# Microcontroller.net
KiCad netlist of a schematic drawn in Altium Designer
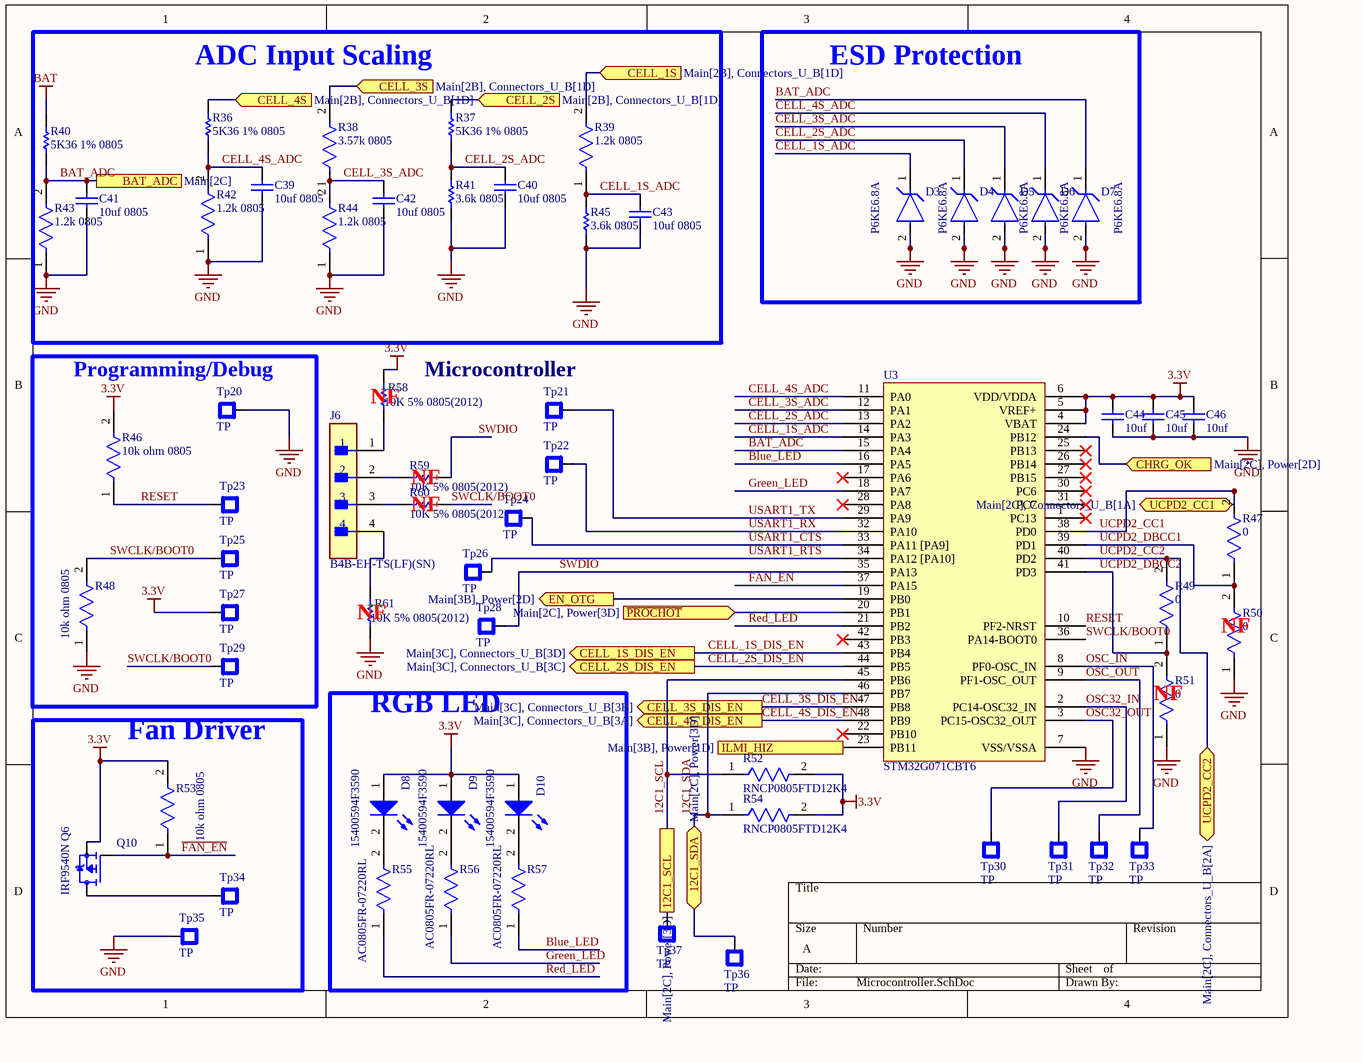
[diagram p0: Microcontroller.SchDoc]

(export (version "E")
  (design (tool "Eeschema 10.0.6"))
  (components
    (comp (ref "C39")
      (value "10uf 0805")
      (footprint "CAPC2013X145X50NL20T20")
      (fields (field (name "PART NUMBER") "VJ0805Y105KXQRW1BC") (field (name "MANUFACTURER") "Vitramon"))
      (libsource (lib "Altium Content Vault") (part "CAP"))
    )
    (comp (ref "C40")
      (value "10uf 0805")
      (footprint "CAPC2013X145X50NL20T20")
      (fields (field (name "PART NUMBER") "VJ0805Y105KXQRW1BC") (field (name "MANUFACTURER") "Vitramon"))
      (libsource (lib "Altium Content Vault") (part "CAP"))
    )
    (comp (ref "C41")
      (value "10uf 0805")
      (footprint "CAPC2013X145X50NL20T20")
      (fields (field (name "PART NUMBER") "VJ0805Y105KXQRW1BC") (field (name "MANUFACTURER") "Vitramon"))
      (libsource (lib "Altium Content Vault") (part "CAP"))
    )
    (comp (ref "C42")
      (value "10uf 0805")
      (footprint "CAPC2013X145X50NL20T20")
      (fields (field (name "PART NUMBER") "VJ0805Y105KXQRW1BC") (field (name "MANUFACTURER") "Vitramon"))
      (libsource (lib "Altium Content Vault") (part "CAP"))
    )
    (comp (ref "C43")
      (value "10uf 0805")
      (footprint "CAPC2013X145X50NL20T20")
      (fields (field (name "PART NUMBER") "VJ0805Y105KXQRW1BC") (field (name "MANUFACTURER") "Vitramon"))
      (libsource (lib "Altium Content Vault") (part "CAP"))
    )
    (comp (ref "C44")
      (value "10uf")
      (footprint "CAPC2013X145X50LL20T25")
      (fields (field (name "MANUFACTURER") "Kemet") (field (name "PART NUMBER") "C0805C106K8RACTU"))
      (libsource (lib "Altium Content Vault") (part "CAP"))
    )
    (comp (ref "C45")
      (value "10uf")
      (footprint "CAPC2013X145X50LL20T25")
      (fields (field (name "MANUFACTURER") "Kemet") (field (name "PART NUMBER") "C0805C106K8RACTU"))
      (libsource (lib "Altium Content Vault") (part "CAP"))
    )
    (comp (ref "C46")
      (value "10uf")
      (footprint "CAPC2013X145X50LL20T25")
      (fields (field (name "MANUFACTURER") "Kemet") (field (name "PART NUMBER") "C0805C106K8RACTU"))
      (libsource (lib "Altium Content Vault") (part "CAP"))
    )
    (comp (ref "D3")
      (value "P6KE6.8A")
      (footprint "FP-P6KE-MFG")
      (description "TVS DIODE 5.8V 10.5V DO204AC")
      (fields
        (field (name "MANUFACTURER") "Littelfuse Inc")
        (field (name "OCTOPART") "https://octopart.com/p6ke6.8a-littelfuse-20808")
      )
      (libsource (lib "Altium Content Vault") (part "f813f71cba58e380607f5dd3caf9714"))
    )
    (comp (ref "D4")
      (value "P6KE6.8A")
      (footprint "FP-P6KE-MFG")
      (description "TVS DIODE 5.8V 10.5V DO204AC")
      (fields
        (field (name "MANUFACTURER") "Littelfuse Inc")
        (field (name "OCTOPART") "https://octopart.com/p6ke6.8a-littelfuse-20808")
      )
      (libsource (lib "Altium Content Vault") (part "f813f71cba58e380607f5dd3caf9714"))
    )
    (comp (ref "D5")
      (value "P6KE6.8A")
      (footprint "FP-P6KE-MFG")
      (description "TVS DIODE 5.8V 10.5V DO204AC")
      (fields
        (field (name "MANUFACTURER") "Littelfuse Inc")
        (field (name "OCTOPART") "https://octopart.com/p6ke6.8a-littelfuse-20808")
      )
      (libsource (lib "Altium Content Vault") (part "f813f71cba58e380607f5dd3caf9714"))
    )
    (comp (ref "D6")
      (value "P6KE6.8A")
      (footprint "FP-P6KE-MFG")
      (description "TVS DIODE 5.8V 10.5V DO204AC")
      (fields
        (field (name "MANUFACTURER") "Littelfuse Inc")
        (field (name "OCTOPART") "https://octopart.com/p6ke6.8a-littelfuse-20808")
      )
      (libsource (lib "Altium Content Vault") (part "f813f71cba58e380607f5dd3caf9714"))
    )
    (comp (ref "D7")
      (value "P6KE6.8A")
      (footprint "FP-P6KE-MFG")
      (description "TVS DIODE 5.8V 10.5V DO204AC")
      (fields
        (field (name "MANUFACTURER") "Littelfuse Inc")
        (field (name "OCTOPART") "https://octopart.com/p6ke6.8a-littelfuse-20808")
      )
      (libsource (lib "Altium Content Vault") (part "f813f71cba58e380607f5dd3caf9714"))
    )
    (comp (ref "D8")
      (value "15400594F3590")
      (footprint "WL-TIRC_5mm")
      (description "Led, 5Mm, 940Nm, 30Mw/Sr, Th Rohs Compliant: Yes")
      (libsource (lib "Altium Content Vault") (part "LED_Infrared_1A-2K"))
    )
    (comp (ref "D9")
      (value "15400594F3590")
      (footprint "WL-TIRC_5mm")
      (description "Led, 5Mm, 940Nm, 30Mw/Sr, Th Rohs Compliant: Yes")
      (libsource (lib "Altium Content Vault") (part "LED_Infrared_1A-2K"))
    )
    (comp (ref "D10")
      (value "15400594F3590")
      (footprint "WL-TIRC_5mm")
      (description "Led, 5Mm, 940Nm, 30Mw/Sr, Th Rohs Compliant: Yes")
      (libsource (lib "Altium Content Vault") (part "LED_Infrared_1A-2K"))
    )
    (comp (ref "J6")
      (value "B4B-EH-TS(LF)(SN)")
      (footprint "FP-B4B-EH-TS_LF_SN-MFG")
      (description "CONN HEADER EH TOP 4POS 2.5MM")
      (libsource (lib "Altium Content Vault") (part "299a8cea1bdcbc3624fe62c390fa72c"))
    )
    (comp (ref "Q10")
      (value "IRF9540N Q6")
      (footprint "TO254P1041X444X1930-3")
      (description "P-Channel 100 V 23A (Tc) 3.1W (Ta), 110W (Tc)")
      (fields (field (name "MF") "Infineon Technologies") (field (name "MP") "IRF9540N"))
      (libsource (lib "power_schi") (part "IRF9540N Q6"))
    )
    (comp (ref "R36")
      (value "5K36 1% 0805")
      (footprint "RESC0805(2012)_M")
      (description "5K36 0.125W 1% 0805 (2012 Metric)  SMD")
      (fields (field (name "POWER") "0.125 W") (field (name "TOLERANCE") "1 %"))
      (libsource (lib "Altium Content Vault") (part "RES"))
    )
    (comp (ref "R37")
      (value "5K36 1% 0805")
      (footprint "RESC0805(2012)_M")
      (description "5K36 0.125W 1% 0805 (2012 Metric)  SMD")
      (fields (field (name "POWER") "0.125 W") (field (name "TOLERANCE") "1 %"))
      (libsource (lib "Altium Content Vault") (part "RES"))
    )
    (comp (ref "R38")
      (value "3.57k 0805")
      (footprint "FP-RT0805-MFG")
      (description "RES 357K OHM 1/8W .1% SMD 0805")
      (fields
        (field (name "OCTOPART") "https://octopart.com/rt0805brd07357kl-yageo-1483813")
        (field (name "MANUFACTURER") "Yageo")
      )
      (libsource (lib "Altium Content Vault") (part "1029c3af85768c4190bb7ad29bc67b5"))
    )
    (comp (ref "R39")
      (value "1.2k 0805")
      (footprint "FP-RMCF0805-IPC_A")
      (description "1.2kΩ ±5% 0.125W 0805 Thick Film Chip Resistor AEC-Q200 compliant")
      (fields (field (name "TOLERANCE") "5%"))
      (libsource (lib "Altium Content Vault") (part "1029c3af85768c4190bb7ad29bc67b5"))
    )
    (comp (ref "R40")
      (value "5K36 1% 0805")
      (footprint "RESC0805(2012)_M")
      (description "5K36 0.125W 1% 0805 (2012 Metric)  SMD")
      (fields (field (name "POWER") "0.125 W") (field (name "TOLERANCE") "1 %"))
      (libsource (lib "Altium Content Vault") (part "RES"))
    )
    (comp (ref "R41")
      (value "3.6k 0805")
      (footprint "RESC0805(2012)_L")
      (description "3K6 0.125W 5% 0805 (2012 Metric)  SMD")
      (fields (field (name "TOLERANCE") "5 %") (field (name "POWER") "0.125 W"))
      (libsource (lib "Altium Content Vault") (part "RES"))
    )
    (comp (ref "R42")
      (value "1.2k 0805")
      (footprint "FP-RMCF0805-IPC_A")
      (description "1.2kΩ ±5% 0.125W 0805 Thick Film Chip Resistor AEC-Q200 compliant")
      (fields (field (name "TOLERANCE") "5%"))
      (libsource (lib "Altium Content Vault") (part "1029c3af85768c4190bb7ad29bc67b5"))
    )
    (comp (ref "R43")
      (value "1.2k 0805")
      (footprint "FP-RMCF0805-IPC_A")
      (description "1.2kΩ ±5% 0.125W 0805 Thick Film Chip Resistor AEC-Q200 compliant")
      (fields (field (name "TOLERANCE") "5%"))
      (libsource (lib "Altium Content Vault") (part "1029c3af85768c4190bb7ad29bc67b5"))
    )
    (comp (ref "R44")
      (value "1.2k 0805")
      (footprint "FP-RMCF0805-IPC_A")
      (description "1.2kΩ ±5% 0.125W 0805 Thick Film Chip Resistor AEC-Q200 compliant")
      (fields (field (name "TOLERANCE") "5%"))
      (libsource (lib "Altium Content Vault") (part "1029c3af85768c4190bb7ad29bc67b5"))
    )
    (comp (ref "R45")
      (value "3.6k 0805")
      (footprint "RESC0805(2012)_L")
      (description "3K6 0.125W 5% 0805 (2012 Metric)  SMD")
      (fields (field (name "TOLERANCE") "5 %") (field (name "POWER") "0.125 W"))
      (libsource (lib "Altium Content Vault") (part "RES"))
    )
    (comp (ref "R46")
      (value "10k ohm 0805")
      (footprint "FP-MCU0805-IPC_C")
      (description "RES 1.05K OHM 0.5% 1/5W 0805")
      (fields (field (name "TOLERANCE") "0.1%"))
      (libsource (lib "Altium Content Vault") (part "1029c3af85768c4190bb7ad29bc67b5"))
    )
    (comp (ref "R47")
      (value "0")
      (footprint "FP-HCJ0805-MFG")
      (description "RES 0 OHM JUMPER 1/2W 0805")
      (libsource (lib "Altium Content Vault") (part "1029c3af85768c4190bb7ad29bc67b5"))
    )
    (comp (ref "R48")
      (value "10k ohm 0805")
      (footprint "FP-MCU0805-IPC_C")
      (description "RES 1.05K OHM 0.5% 1/5W 0805")
      (fields (field (name "TOLERANCE") "0.1%"))
      (libsource (lib "Altium Content Vault") (part "1029c3af85768c4190bb7ad29bc67b5"))
    )
    (comp (ref "R49")
      (value "0")
      (footprint "FP-HCJ0805-MFG")
      (description "RES 0 OHM JUMPER 1/2W 0805")
      (libsource (lib "Altium Content Vault") (part "1029c3af85768c4190bb7ad29bc67b5"))
    )
    (comp (ref "R50")
      (value "0")
      (footprint "FP-HCJ0805-MFG")
      (description "RES 0 OHM JUMPER 1/2W 0805")
      (libsource (lib "Altium Content Vault") (part "1029c3af85768c4190bb7ad29bc67b5"))
    )
    (comp (ref "R51")
      (value "0")
      (footprint "FP-HCJ0805-MFG")
      (description "RES 0 OHM JUMPER 1/2W 0805")
      (libsource (lib "Altium Content Vault") (part "1029c3af85768c4190bb7ad29bc67b5"))
    )
    (comp (ref "R52")
      (value "RNCP0805FTD12K4")
      (footprint "FP-RNCP0805-IPC_C")
      (description "12.4kΩ ±1% 0.25W 0805 High Power Anti-Sulfur Thin Film Chip Resistor")
      (fields (field (name "TOLERANCE") "1%"))
      (libsource (lib "Altium Content Vault") (part "1029c3af85768c4190bb7ad29bc67b5"))
    )
    (comp (ref "R53")
      (value "10k ohm 0805")
      (footprint "FP-MCU0805-IPC_C")
      (description "RES 1.05K OHM 0.5% 1/5W 0805")
      (fields (field (name "TOLERANCE") "0.1%"))
      (libsource (lib "Altium Content Vault") (part "1029c3af85768c4190bb7ad29bc67b5"))
    )
    (comp (ref "R54")
      (value "RNCP0805FTD12K4")
      (footprint "FP-RNCP0805-IPC_C")
      (description "12.4kΩ ±1% 0.25W 0805 High Power Anti-Sulfur Thin Film Chip Resistor")
      (fields (field (name "TOLERANCE") "1%"))
      (libsource (lib "Altium Content Vault") (part "1029c3af85768c4190bb7ad29bc67b5"))
    )
    (comp (ref "R55")
      (value "AC0805FR-07220RL")
      (footprint "FP-AC0805-MFG")
      (description "RES SMD 220 OHM 1% 1/8W 0805")
      (fields
        (field (name "OCTOPART") "https://octopart.com/ac0805fr-07220rl-yageo-26041145")
        (field (name "TOLERANCE") "0.01")
      )
      (libsource (lib "Altium Content Vault") (part "1029c3af85768c4190bb7ad29bc67b5"))
    )
    (comp (ref "R56")
      (value "AC0805FR-07220RL")
      (footprint "FP-AC0805-MFG")
      (description "RES SMD 220 OHM 1% 1/8W 0805")
      (fields
        (field (name "OCTOPART") "https://octopart.com/ac0805fr-07220rl-yageo-26041145")
        (field (name "TOLERANCE") "0.01")
      )
      (libsource (lib "Altium Content Vault") (part "1029c3af85768c4190bb7ad29bc67b5"))
    )
    (comp (ref "R57")
      (value "AC0805FR-07220RL")
      (footprint "FP-AC0805-MFG")
      (description "RES SMD 220 OHM 1% 1/8W 0805")
      (fields
        (field (name "OCTOPART") "https://octopart.com/ac0805fr-07220rl-yageo-26041145")
        (field (name "TOLERANCE") "0.01")
      )
      (libsource (lib "Altium Content Vault") (part "1029c3af85768c4190bb7ad29bc67b5"))
    )
    (comp (ref "R58")
      (value "10K 5% 0805(2012)")
      (footprint "RESC0805(2012)_L")
      (description "10K 0.125W 5% 0805 (2012 Metric)  SMD")
      (fields (field (name "POWER") "0.125 W") (field (name "TOLERANCE") "5 %"))
      (libsource (lib "Altium Content Vault") (part "RES"))
    )
    (comp (ref "R59")
      (value "10K 5% 0805(2012)")
      (footprint "RESC0805(2012)_L")
      (description "10K 0.125W 5% 0805 (2012 Metric)  SMD")
      (fields (field (name "POWER") "0.125 W") (field (name "TOLERANCE") "5 %"))
      (libsource (lib "Altium Content Vault") (part "RES"))
    )
    (comp (ref "R60")
      (value "10K 5% 0805(2012)")
      (footprint "RESC0805(2012)_L")
      (description "10K 0.125W 5% 0805 (2012 Metric)  SMD")
      (fields (field (name "POWER") "0.125 W") (field (name "TOLERANCE") "5 %"))
      (libsource (lib "Altium Content Vault") (part "RES"))
    )
    (comp (ref "R61")
      (value "10K 5% 0805(2012)")
      (footprint "RESC0805(2012)_L")
      (description "10K 0.125W 5% 0805 (2012 Metric)  SMD")
      (fields (field (name "POWER") "0.125 W") (field (name "TOLERANCE") "5 %"))
      (libsource (lib "Altium Content Vault") (part "RES"))
    )
    (comp (ref "Tp20") (value "TP") (footprint "Tp") (libsource (lib "power_schi") (part "TP")))
    (comp (ref "Tp21") (value "TP") (footprint "Tp") (libsource (lib "power_schi") (part "TP")))
    (comp (ref "Tp22") (value "TP") (footprint "Tp") (libsource (lib "power_schi") (part "TP")))
    (comp (ref "Tp23") (value "TP") (footprint "Tp") (libsource (lib "power_schi") (part "TP")))
    (comp (ref "Tp24") (value "TP") (footprint "Tp") (libsource (lib "power_schi") (part "TP")))
    (comp (ref "Tp25") (value "TP") (footprint "Tp") (libsource (lib "power_schi") (part "TP")))
    (comp (ref "Tp26") (value "TP") (footprint "Tp") (libsource (lib "power_schi") (part "TP")))
    (comp (ref "Tp27") (value "TP") (footprint "Tp") (libsource (lib "power_schi") (part "TP")))
    (comp (ref "Tp28") (value "TP") (footprint "Tp") (libsource (lib "power_schi") (part "TP")))
    (comp (ref "Tp29") (value "TP") (footprint "Tp") (libsource (lib "power_schi") (part "TP")))
    (comp (ref "Tp30") (value "TP") (footprint "Tp") (libsource (lib "power_schi") (part "TP")))
    (comp (ref "Tp31") (value "TP") (footprint "Tp") (libsource (lib "power_schi") (part "TP")))
    (comp (ref "Tp32") (value "TP") (footprint "Tp") (libsource (lib "power_schi") (part "TP")))
    (comp (ref "Tp33") (value "TP") (footprint "Tp") (libsource (lib "power_schi") (part "TP")))
    (comp (ref "Tp34") (value "TP") (footprint "Tp") (libsource (lib "power_schi") (part "TP")))
    (comp (ref "Tp35") (value "TP") (footprint "Tp") (libsource (lib "power_schi") (part "TP")))
    (comp (ref "Tp36") (value "TP") (footprint "Tp") (libsource (lib "power_schi") (part "TP")))
    (comp (ref "Tp37") (value "TP") (footprint "Tp") (libsource (lib "power_schi") (part "TP")))
    (comp (ref "U3")
      (value "STM32G071CBT6")
      (footprint "QFP50P900X900X160-48N")
      (description "MCU 32-bit ARM Cortex M0+ RISC 128KB Flash 1.8V/2.5V/3.3V 48-Pin LQFP Tray")
      (fields (field (name "MANUFACTURER") "STMicroelectronics"))
      (libsource (lib "power_schi") (part "STM32G071CBT6"))
    )
  )
  (nets
    (net (code "1") (name "/12C1_SCL") (class "Default")
      (node (ref "R52") (pin "1") (pinfunction "1_1") (pintype "passive"))
      (node (ref "Tp37") (pin "1") (pinfunction "1_1") (pintype "passive"))
      (node (ref "U3") (pin "45") (pinfunction "PB6_45") (pintype "passive"))
    )
    (net (code "2") (name "/12C1_SDA") (class "Default")
      (node (ref "R54") (pin "1") (pinfunction "1_1") (pintype "passive"))
      (node (ref "Tp36") (pin "1") (pinfunction "1_1") (pintype "passive"))
      (node (ref "U3") (pin "46") (pinfunction "PB7_46") (pintype "passive"))
    )
    (net (code "3") (name "/BAT_ADC") (class "Default")
      (node (ref "C41") (pin "2") (pinfunction "2_2") (pintype "passive"))
      (node (ref "D7") (pin "1") (pinfunction "C_1") (pintype "passive"))
      (node (ref "R40") (pin "1") (pinfunction "1_1") (pintype "passive"))
      (node (ref "R43") (pin "2") (pinfunction "2_2") (pintype "passive"))
      (node (ref "U3") (pin "15") (pinfunction "PA4_15") (pintype "passive"))
    )
    (net (code "4") (name "/Blue_LED") (class "Default")
      (node (ref "R57") (pin "1") (pinfunction "1_1") (pintype "passive"))
      (node (ref "U3") (pin "16") (pinfunction "PA5_16") (pintype "passive"))
    )
    (net (code "5") (name "/CELL_1S") (class "Default")
      (node (ref "R39") (pin "2") (pinfunction "2_2") (pintype "passive"))
    )
    (net (code "6") (name "/CELL_1S_ADC") (class "Default")
      (node (ref "C43") (pin "2") (pinfunction "2_2") (pintype "passive"))
      (node (ref "D3") (pin "1") (pinfunction "C_1") (pintype "passive"))
      (node (ref "R39") (pin "1") (pinfunction "1_1") (pintype "passive"))
      (node (ref "R45") (pin "2") (pinfunction "2_2") (pintype "passive"))
      (node (ref "U3") (pin "14") (pinfunction "PA3_14") (pintype "passive"))
    )
    (net (code "7") (name "/CELL_1S_DIS_EN") (class "Default")
      (node (ref "U3") (pin "43") (pinfunction "PB4_43") (pintype "passive"))
    )
    (net (code "8") (name "/CELL_2S") (class "Default")
      (node (ref "R37") (pin "2") (pinfunction "2_2") (pintype "passive"))
    )
    (net (code "9") (name "/CELL_2S_ADC") (class "Default")
      (node (ref "C40") (pin "2") (pinfunction "2_2") (pintype "passive"))
      (node (ref "D4") (pin "1") (pinfunction "C_1") (pintype "passive"))
      (node (ref "R37") (pin "1") (pinfunction "1_1") (pintype "passive"))
      (node (ref "R41") (pin "2") (pinfunction "2_2") (pintype "passive"))
      (node (ref "U3") (pin "13") (pinfunction "PA2_13") (pintype "passive"))
    )
    (net (code "10") (name "/CELL_2S_DIS_EN") (class "Default")
      (node (ref "U3") (pin "44") (pinfunction "PB5_44") (pintype "passive"))
    )
    (net (code "11") (name "/CELL_3S") (class "Default")
      (node (ref "R38") (pin "2") (pinfunction "2_2") (pintype "passive"))
    )
    (net (code "12") (name "/CELL_3S_ADC") (class "Default")
      (node (ref "C42") (pin "2") (pinfunction "2_2") (pintype "passive"))
      (node (ref "D5") (pin "1") (pinfunction "C_1") (pintype "passive"))
      (node (ref "R38") (pin "1") (pinfunction "1_1") (pintype "passive"))
      (node (ref "R44") (pin "2") (pinfunction "2_2") (pintype "passive"))
      (node (ref "U3") (pin "12") (pinfunction "PA1_12") (pintype "passive"))
    )
    (net (code "13") (name "/CELL_3S_DIS_EN") (class "Default")
      (node (ref "U3") (pin "47") (pinfunction "PB8_47") (pintype "passive"))
    )
    (net (code "14") (name "/CELL_4S") (class "Default")
      (node (ref "R36") (pin "2") (pinfunction "2_2") (pintype "passive"))
    )
    (net (code "15") (name "/CELL_4S_ADC") (class "Default")
      (node (ref "C39") (pin "2") (pinfunction "2_2") (pintype "passive"))
      (node (ref "D6") (pin "1") (pinfunction "C_1") (pintype "passive"))
      (node (ref "R36") (pin "1") (pinfunction "1_1") (pintype "passive"))
      (node (ref "R42") (pin "2") (pinfunction "2_2") (pintype "passive"))
      (node (ref "U3") (pin "11") (pinfunction "PA0_11") (pintype "passive"))
    )
    (net (code "16") (name "/CELL_4S_DIS_EN") (class "Default")
      (node (ref "U3") (pin "48") (pinfunction "PB9_48") (pintype "passive"))
    )
    (net (code "17") (name "/CHRG_OK") (class "Default")
      (node (ref "U3") (pin "24") (pinfunction "PB12_24") (pintype "passive"))
    )
    (net (code "18") (name "/EN_OTG") (class "Default")
      (node (ref "U3") (pin "19") (pinfunction "PB0_19") (pintype "passive"))
    )
    (net (code "19") (name "/Green_LED") (class "Default")
      (node (ref "R56") (pin "1") (pinfunction "1_1") (pintype "passive"))
      (node (ref "U3") (pin "18") (pinfunction "PA7_18") (pintype "passive"))
    )
    (net (code "20") (name "/ILMI_HIZ") (class "Default")
      (node (ref "U3") (pin "23") (pinfunction "PB11_23") (pintype "passive"))
    )
    (net (code "21") (name "/OSC32_IN") (class "Default")
      (node (ref "Tp31") (pin "1") (pinfunction "1_1") (pintype "passive"))
      (node (ref "U3") (pin "2") (pinfunction "PC14-OSC32_IN_2") (pintype "passive"))
    )
    (net (code "22") (name "/OSC32_OUT") (class "Default")
      (node (ref "Tp30") (pin "1") (pinfunction "1_1") (pintype "passive"))
      (node (ref "U3") (pin "3") (pinfunction "PC15-OSC32_OUT_3") (pintype "passive"))
    )
    (net (code "23") (name "/OSC_IN") (class "Default")
      (node (ref "Tp33") (pin "1") (pinfunction "1_1") (pintype "passive"))
      (node (ref "U3") (pin "8") (pinfunction "PF0-OSC_IN_8") (pintype "passive"))
    )
    (net (code "24") (name "/OSC_OUT") (class "Default")
      (node (ref "Tp32") (pin "1") (pinfunction "1_1") (pintype "passive"))
      (node (ref "U3") (pin "9") (pinfunction "PF1-OSC_OUT_9") (pintype "passive"))
    )
    (net (code "25") (name "/RESET") (class "Default")
      (node (ref "R46") (pin "1") (pinfunction "1_1") (pintype "passive"))
      (node (ref "Tp23") (pin "1") (pinfunction "1_1") (pintype "passive"))
      (node (ref "U3") (pin "10") (pinfunction "PF2-NRST_10") (pintype "passive"))
    )
    (net (code "26") (name "/Red_LED") (class "Default")
      (node (ref "R55") (pin "1") (pinfunction "1_1") (pintype "passive"))
      (node (ref "U3") (pin "21") (pinfunction "PB2_21") (pintype "passive"))
    )
    (net (code "27") (name "/SWCLK{slash}BOOT0") (class "Default")
      (node (ref "R48") (pin "2") (pinfunction "2_2") (pintype "passive"))
      (node (ref "R60") (pin "2") (pinfunction "2_2") (pintype "passive"))
      (node (ref "Tp25") (pin "1") (pinfunction "1_1") (pintype "passive"))
      (node (ref "Tp29") (pin "1") (pinfunction "1_1") (pintype "passive"))
      (node (ref "U3") (pin "36") (pinfunction "PA14-BOOT0_36") (pintype "passive"))
    )
    (net (code "28") (name "/SWDIO") (class "Default")
      (node (ref "R59") (pin "2") (pinfunction "2_2") (pintype "passive"))
      (node (ref "Tp28") (pin "1") (pinfunction "1_1") (pintype "passive"))
      (node (ref "U3") (pin "35") (pinfunction "PA13_35") (pintype "passive"))
    )
    (net (code "29") (name "/UCPD2_CC1") (class "Default")
      (node (ref "R47") (pin "2") (pinfunction "2_2") (pintype "passive"))
      (node (ref "U3") (pin "38") (pinfunction "PD0_38") (pintype "passive"))
    )
    (net (code "30") (name "/UCPD2_CC2") (class "Default")
      (node (ref "R49") (pin "2") (pinfunction "2_2") (pintype "passive"))
      (node (ref "U3") (pin "40") (pinfunction "PD2_40") (pintype "passive"))
    )
    (net (code "31") (name "/UCPD2_DBCC1") (class "Default")
      (node (ref "R47") (pin "1") (pinfunction "1_1") (pintype "passive"))
      (node (ref "R50") (pin "2") (pinfunction "2_2") (pintype "passive"))
      (node (ref "U3") (pin "39") (pinfunction "PD1_39") (pintype "passive"))
    )
    (net (code "32") (name "/UCPD2_DBCC2") (class "Default")
      (node (ref "R49") (pin "1") (pinfunction "1_1") (pintype "passive"))
      (node (ref "R51") (pin "2") (pinfunction "2_2") (pintype "passive"))
      (node (ref "U3") (pin "41") (pinfunction "PD3_41") (pintype "passive"))
    )
    (net (code "33") (name "/USART1_CTS") (class "Default")
      (node (ref "Tp24") (pin "1") (pinfunction "1_1") (pintype "passive"))
      (node (ref "U3") (pin "33") (pinfunction "PA11_[PA9]_33") (pintype "passive"))
    )
    (net (code "34") (name "/USART1_RTS") (class "Default")
      (node (ref "Tp26") (pin "1") (pinfunction "1_1") (pintype "passive"))
      (node (ref "U3") (pin "34") (pinfunction "PA12_[PA10]_34") (pintype "passive"))
    )
    (net (code "35") (name "/USART1_RX") (class "Default")
      (node (ref "Tp22") (pin "1") (pinfunction "1_1") (pintype "passive"))
      (node (ref "U3") (pin "32") (pinfunction "PA10_32") (pintype "passive"))
    )
    (net (code "36") (name "/USART1_TX") (class "Default")
      (node (ref "Tp21") (pin "1") (pinfunction "1_1") (pintype "passive"))
      (node (ref "U3") (pin "29") (pinfunction "PA9_29") (pintype "passive"))
    )
    (net (code "37") (name "/~{FAN_EN}") (class "Default")
      (node (ref "Q10") (pin "1") (pinfunction "G_1") (pintype "passive"))
      (node (ref "R53") (pin "1") (pinfunction "1_1") (pintype "passive"))
      (node (ref "U3") (pin "37") (pinfunction "PA15_37") (pintype "passive"))
    )
    (net (code "38") (name "/~{PROCHOT}") (class "Default")
      (node (ref "U3") (pin "20") (pinfunction "PB1_20") (pintype "passive"))
    )
    (net (code "39") (name "3.3V") (class "Default")
      (node (ref "C44") (pin "2") (pinfunction "2_2") (pintype "passive"))
      (node (ref "C45") (pin "2") (pinfunction "2_2") (pintype "passive"))
      (node (ref "C46") (pin "2") (pinfunction "2_2") (pintype "passive"))
      (node (ref "D10") (pin "1") (pinfunction "A_1") (pintype "passive"))
      (node (ref "D8") (pin "1") (pinfunction "A_1") (pintype "passive"))
      (node (ref "D9") (pin "1") (pinfunction "A_1") (pintype "passive"))
      (node (ref "Q10") (pin "3") (pinfunction "S_3") (pintype "passive"))
      (node (ref "R46") (pin "2") (pinfunction "2_2") (pintype "passive"))
      (node (ref "R52") (pin "2") (pinfunction "2_2") (pintype "passive"))
      (node (ref "R53") (pin "2") (pinfunction "2_2") (pintype "passive"))
      (node (ref "R54") (pin "2") (pinfunction "2_2") (pintype "passive"))
      (node (ref "R58") (pin "2") (pinfunction "2_2") (pintype "passive"))
      (node (ref "Tp27") (pin "1") (pinfunction "1_1") (pintype "passive"))
      (node (ref "U3") (pin "4") (pinfunction "VBAT_4") (pintype "passive"))
      (node (ref "U3") (pin "5") (pinfunction "VREF+_5") (pintype "passive"))
      (node (ref "U3") (pin "6") (pinfunction "VDD/VDDA_6") (pintype "passive"))
    )
    (net (code "40") (name "BAT") (class "Default")
      (node (ref "R40") (pin "2") (pinfunction "2_2") (pintype "passive"))
    )
    (net (code "41") (name "GND") (class "Default")
      (node (ref "C39") (pin "1") (pinfunction "1_1") (pintype "passive"))
      (node (ref "C40") (pin "1") (pinfunction "1_1") (pintype "passive"))
      (node (ref "C41") (pin "1") (pinfunction "1_1") (pintype "passive"))
      (node (ref "C42") (pin "1") (pinfunction "1_1") (pintype "passive"))
      (node (ref "C43") (pin "1") (pinfunction "1_1") (pintype "passive"))
      (node (ref "C44") (pin "1") (pinfunction "1_1") (pintype "passive"))
      (node (ref "C45") (pin "1") (pinfunction "1_1") (pintype "passive"))
      (node (ref "C46") (pin "1") (pinfunction "1_1") (pintype "passive"))
      (node (ref "D3") (pin "2") (pinfunction "A_2") (pintype "passive"))
      (node (ref "D4") (pin "2") (pinfunction "A_2") (pintype "passive"))
      (node (ref "D5") (pin "2") (pinfunction "A_2") (pintype "passive"))
      (node (ref "D6") (pin "2") (pinfunction "A_2") (pintype "passive"))
      (node (ref "D7") (pin "2") (pinfunction "A_2") (pintype "passive"))
      (node (ref "R41") (pin "1") (pinfunction "1_1") (pintype "passive"))
      (node (ref "R42") (pin "1") (pinfunction "1_1") (pintype "passive"))
      (node (ref "R43") (pin "1") (pinfunction "1_1") (pintype "passive"))
      (node (ref "R44") (pin "1") (pinfunction "1_1") (pintype "passive"))
      (node (ref "R45") (pin "1") (pinfunction "1_1") (pintype "passive"))
      (node (ref "R48") (pin "1") (pinfunction "1_1") (pintype "passive"))
      (node (ref "R50") (pin "1") (pinfunction "1_1") (pintype "passive"))
      (node (ref "R51") (pin "1") (pinfunction "1_1") (pintype "passive"))
      (node (ref "R61") (pin "1") (pinfunction "1_1") (pintype "passive"))
      (node (ref "Tp20") (pin "1") (pinfunction "1_1") (pintype "passive"))
      (node (ref "Tp35") (pin "1") (pinfunction "1_1") (pintype "passive"))
      (node (ref "U3") (pin "7") (pinfunction "VSS/VSSA_7") (pintype "passive"))
    )
    (net (code "42") (name "Net-(D8-K)") (class "Default")
      (node (ref "D8") (pin "2") (pinfunction "K_2") (pintype "passive"))
      (node (ref "R55") (pin "2") (pinfunction "2_2") (pintype "passive"))
    )
    (net (code "43") (name "Net-(D9-K)") (class "Default")
      (node (ref "D9") (pin "2") (pinfunction "K_2") (pintype "passive"))
      (node (ref "R56") (pin "2") (pinfunction "2_2") (pintype "passive"))
    )
    (net (code "44") (name "Net-(D10-K)") (class "Default")
      (node (ref "D10") (pin "2") (pinfunction "K_2") (pintype "passive"))
      (node (ref "R57") (pin "2") (pinfunction "2_2") (pintype "passive"))
    )
    (net (code "45") (name "Net-(J6-Pad1)") (class "Default")
      (node (ref "J6") (pin "1") (pinfunction "1_1") (pintype "passive"))
      (node (ref "R58") (pin "1") (pinfunction "1_1") (pintype "passive"))
    )
    (net (code "46") (name "Net-(J6-Pad2)") (class "Default")
      (node (ref "J6") (pin "2") (pinfunction "2_2") (pintype "passive"))
      (node (ref "R59") (pin "1") (pinfunction "1_1") (pintype "passive"))
    )
    (net (code "47") (name "Net-(J6-Pad3)") (class "Default")
      (node (ref "J6") (pin "3") (pinfunction "3_3") (pintype "passive"))
      (node (ref "R60") (pin "1") (pinfunction "1_1") (pintype "passive"))
    )
    (net (code "48") (name "Net-(J6-Pad4)") (class "Default")
      (node (ref "J6") (pin "4") (pinfunction "4_4") (pintype "passive"))
      (node (ref "R61") (pin "2") (pinfunction "2_2") (pintype "passive"))
    )
    (net (code "49") (name "Net-(Q10-D)") (class "Default")
      (node (ref "Q10") (pin "2") (pinfunction "D_2") (pintype "passive"))
      (node (ref "Tp34") (pin "1") (pinfunction "1_1") (pintype "passive"))
    )
    (net (code "50") (name "unconnected-(U3-PA6-Pad17)") (class "Default")
      (node (ref "U3") (pin "17") (pinfunction "PA6_17") (pintype "passive+no_connect"))
    )
    (net (code "51") (name "unconnected-(U3-PA8-Pad28)") (class "Default")
      (node (ref "U3") (pin "28") (pinfunction "PA8_28") (pintype "passive+no_connect"))
    )
    (net (code "52") (name "unconnected-(U3-PB3-Pad42)") (class "Default")
      (node (ref "U3") (pin "42") (pinfunction "PB3_42") (pintype "passive+no_connect"))
    )
    (net (code "53") (name "unconnected-(U3-PB10-Pad22)") (class "Default")
      (node (ref "U3") (pin "22") (pinfunction "PB10_22") (pintype "passive+no_connect"))
    )
    (net (code "54") (name "unconnected-(U3-PB13-Pad25)") (class "Default")
      (node (ref "U3") (pin "25") (pinfunction "PB13_25") (pintype "passive+no_connect"))
    )
    (net (code "55") (name "unconnected-(U3-PB14-Pad26)") (class "Default")
      (node (ref "U3") (pin "26") (pinfunction "PB14_26") (pintype "passive+no_connect"))
    )
    (net (code "56") (name "unconnected-(U3-PB15-Pad27)") (class "Default")
      (node (ref "U3") (pin "27") (pinfunction "PB15_27") (pintype "passive+no_connect"))
    )
    (net (code "57") (name "unconnected-(U3-PC6-Pad30)") (class "Default")
      (node (ref "U3") (pin "30") (pinfunction "PC6_30") (pintype "passive+no_connect"))
    )
    (net (code "58") (name "unconnected-(U3-PC7-Pad31)") (class "Default")
      (node (ref "U3") (pin "31") (pinfunction "PC7_31") (pintype "passive+no_connect"))
    )
    (net (code "59") (name "unconnected-(U3-PC13-Pad1)") (class "Default")
      (node (ref "U3") (pin "1") (pinfunction "PC13_1") (pintype "passive+no_connect"))
    )
  )
)
